# MIDI_Kontakter.net
KiCad netlist of a schematic drawn in Altium Designer
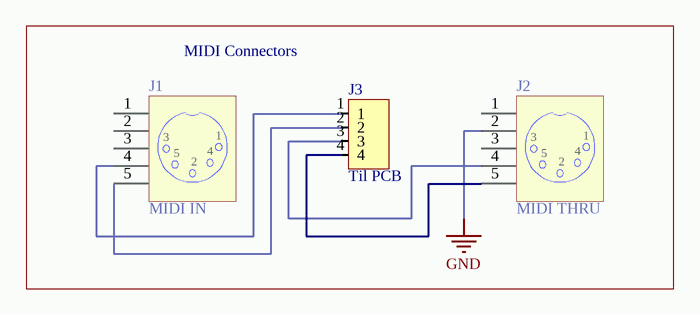
[diagram p0: MIDI_Kontakter.SchDoc]

(export (version "E")
  (design (tool "Eeschema 10.0.6"))
  (components
    (comp (ref "J1")
      (value "MIDI IN")
      (footprint "KONV-KMFCDIN76005_V")
      (description "Socket, 5-way R/A DIN")
      (fields (field (name "MANUFACTURER") "Konvee Electronic") (field (name "PARTNUMBER") "KMFCDIN76005"))
      (libsource (lib "Altium Content Vault") (part "CMP-0406-00001-1"))
    )
    (comp (ref "J2")
      (value "MIDI THRU")
      (footprint "KONV-KMFCDIN76005_V")
      (description "Socket, 5-way R/A DIN")
      (fields (field (name "MANUFACTURER") "Konvee Electronic") (field (name "PARTNUMBER") "KMFCDIN76005"))
      (libsource (lib "Altium Content Vault") (part "CMP-0406-00001-1"))
    )
    (comp (ref "J3") (value "Til PCB") (footprint "JST 4pin") (libsource (lib "Schlib1") (part "JST 4pin")))
  )
  (nets
    (net (code "1") (name "GND") (class "Default")
      (node (ref "J2") (pin "2") (pinfunction "2_2") (pintype "passive"))
    )
    (net (code "2") (name "Net-(J1-Pad4)") (class "Default")
      (node (ref "J1") (pin "4") (pinfunction "4_4") (pintype "passive"))
      (node (ref "J3") (pin "1") (pinfunction "1_1") (pintype "passive"))
    )
    (net (code "3") (name "Net-(J1-Pad5)") (class "Default")
      (node (ref "J1") (pin "5") (pinfunction "5_5") (pintype "passive"))
      (node (ref "J3") (pin "2") (pinfunction "2_2") (pintype "passive"))
    )
    (net (code "4") (name "Net-(J2-Pad4)") (class "Default")
      (node (ref "J2") (pin "4") (pinfunction "4_4") (pintype "passive"))
      (node (ref "J3") (pin "3") (pinfunction "3_3") (pintype "passive"))
    )
    (net (code "5") (name "Net-(J2-Pad5)") (class "Default")
      (node (ref "J2") (pin "5") (pinfunction "5_5") (pintype "passive"))
      (node (ref "J3") (pin "4") (pinfunction "4_4") (pintype "passive"))
    )
    (net (code "6") (name "unconnected-(J1-Pad1)") (class "Default")
      (node (ref "J1") (pin "1") (pinfunction "1_1") (pintype "passive"))
    )
    (net (code "7") (name "unconnected-(J1-Pad2)") (class "Default")
      (node (ref "J1") (pin "2") (pinfunction "2_2") (pintype "passive"))
    )
    (net (code "8") (name "unconnected-(J1-Pad3)") (class "Default")
      (node (ref "J1") (pin "3") (pinfunction "3_3") (pintype "passive"))
    )
    (net (code "9") (name "unconnected-(J1-PadMH1)") (class "Default")
      (node (ref "J1") (pin "MH1") (pinfunction "MH1_MH1") (pintype "passive"))
    )
    (net (code "10") (name "unconnected-(J1-PadMH2)") (class "Default")
      (node (ref "J1") (pin "MH2") (pinfunction "MH2_MH2") (pintype "passive"))
    )
    (net (code "11") (name "unconnected-(J2-Pad1)") (class "Default")
      (node (ref "J2") (pin "1") (pinfunction "1_1") (pintype "passive"))
    )
    (net (code "12") (name "unconnected-(J2-Pad3)") (class "Default")
      (node (ref "J2") (pin "3") (pinfunction "3_3") (pintype "passive"))
    )
    (net (code "13") (name "unconnected-(J2-PadMH1)") (class "Default")
      (node (ref "J2") (pin "MH1") (pinfunction "MH1_MH1") (pintype "passive"))
    )
    (net (code "14") (name "unconnected-(J2-PadMH2)") (class "Default")
      (node (ref "J2") (pin "MH2") (pinfunction "MH2_MH2") (pintype "passive"))
    )
  )
)
